# NixieClockv1_1.net
KiCad netlist of a schematic drawn in Altium Designer
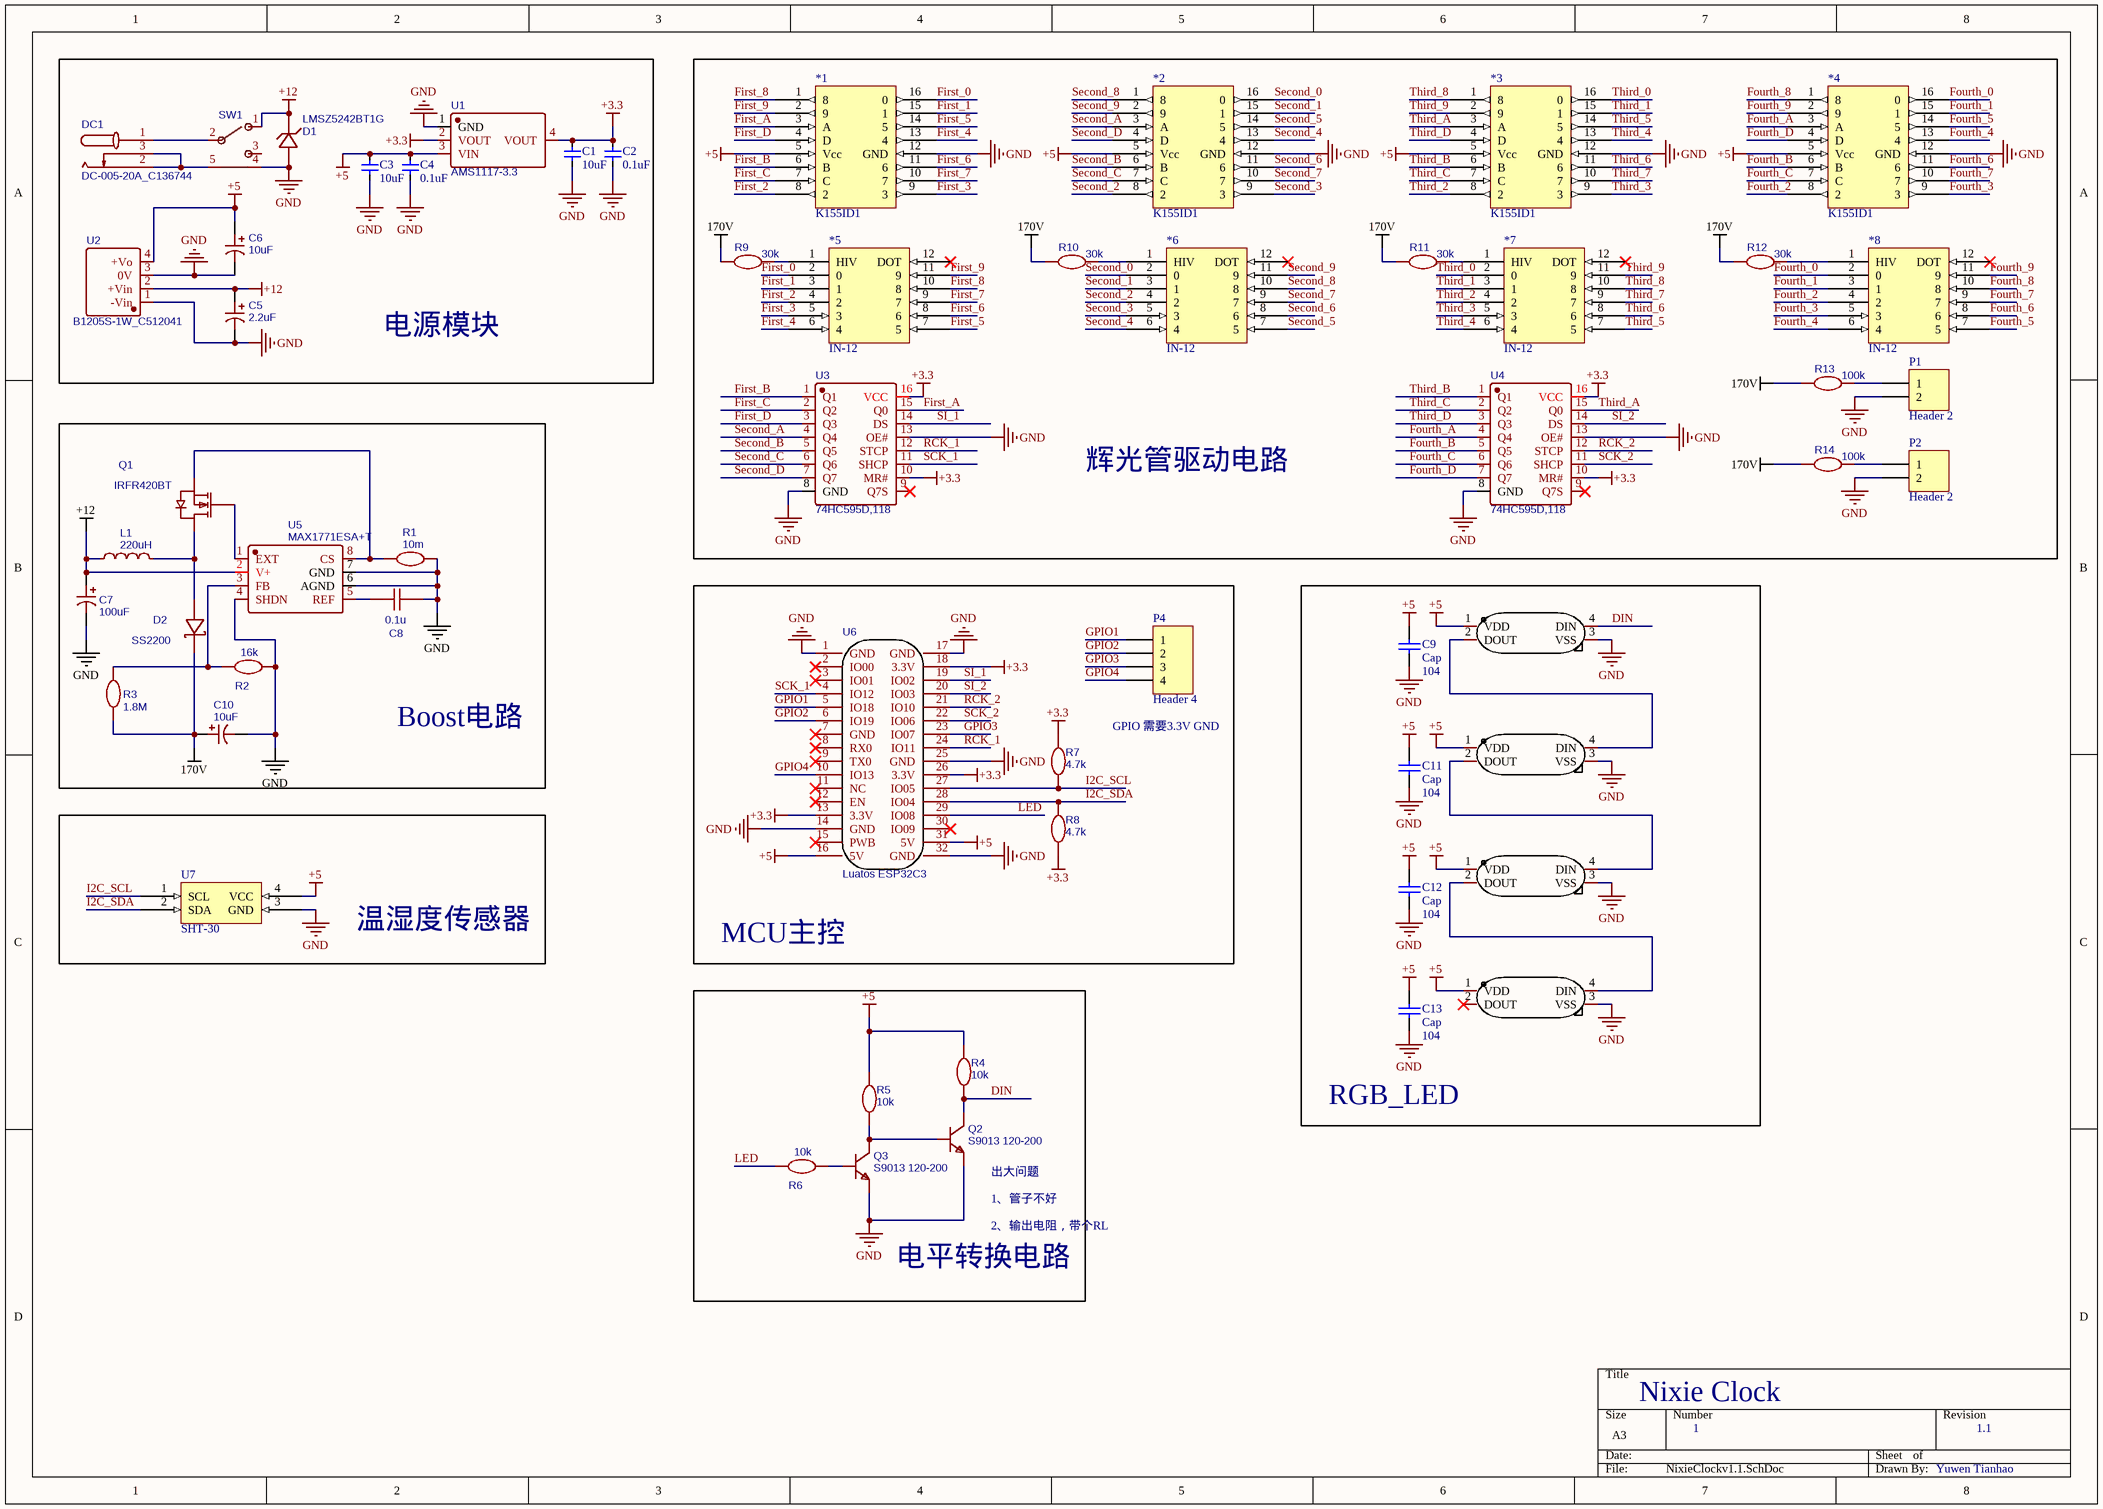
[diagram p0: NixieClockv1.1.SchDoc]

(export (version "E")
  (design (tool "Eeschema 10.0.6"))
  (components
    (comp (ref "*1") (value "K155ID1") (footprint "K155ID1") (libsource (lib "Nixie1") (part "K155ID1")))
    (comp (ref "*2") (value "K155ID1") (footprint "K155ID1") (libsource (lib "Nixie1") (part "K155ID1")))
    (comp (ref "*3") (value "K155ID1") (footprint "K155ID1") (libsource (lib "Nixie1") (part "K155ID1")))
    (comp (ref "*4") (value "K155ID1") (footprint "K155ID1") (libsource (lib "Nixie1") (part "K155ID1")))
    (comp (ref "*5") (value "IN-12") (footprint "IN12") (libsource (lib "Nixie1") (part "IN-12")))
    (comp (ref "*6") (value "IN-12") (footprint "IN12") (libsource (lib "Nixie1") (part "IN-12")))
    (comp (ref "*7") (value "IN-12") (footprint "IN12") (libsource (lib "Nixie1") (part "IN-12")))
    (comp (ref "*8") (value "IN-12") (footprint "IN12") (libsource (lib "Nixie1") (part "IN-12")))
    (comp (ref "C1")
      (value "10uF")
      (footprint "C0805")
      (description "Capacitor")
      (libsource (lib "电容-SCH") (part "C"))
    )
    (comp (ref "C2")
      (value "0.1uF")
      (footprint "0805C")
      (description "Capacitor")
      (libsource (lib "电容-SCH") (part "C"))
    )
    (comp (ref "C3")
      (value "10uF")
      (footprint "0805C")
      (description "Capacitor")
      (libsource (lib "电容-SCH") (part "C"))
    )
    (comp (ref "C4")
      (value "0.1uF")
      (footprint "0805C")
      (description "Capacitor")
      (libsource (lib "电容-SCH") (part "C"))
    )
    (comp (ref "C5")
      (value "2.2uF")
      (footprint "CAP-TH_BD8.0-P3.50-D0.5-FD")
      (fields
        (field (name "BOM_SUPPLIER PART") "C2847238")
        (field (name "BOM_MANUFACTURER PART") "LW100M2500814PE4")
        (field (name "CONTRIBUTOR") "LCSC")
      )
      (libsource (lib "Boost1") (part "10uF"))
    )
    (comp (ref "C6")
      (value "10uF")
      (footprint "CAP-TH_BD8.0-P3.50-D0.5-FD")
      (fields
        (field (name "BOM_SUPPLIER PART") "C2847238")
        (field (name "BOM_MANUFACTURER PART") "LW100M2500814PE4")
        (field (name "CONTRIBUTOR") "LCSC")
      )
      (libsource (lib "Boost1") (part "10uF"))
    )
    (comp (ref "C7")
      (value "100uF")
      (footprint "CAP-TH_BD8.0-P3.50-D0.5-FD")
      (fields
        (field (name "BOM_SUPPLIER PART") "C2847238")
        (field (name "BOM_MANUFACTURER PART") "LW100M2500814PE4")
        (field (name "CONTRIBUTOR") "LCSC")
      )
      (libsource (lib "altium-import") (part "root_3_100uF_"))
    )
    (comp (ref "C8")
      (value "0.1u")
      (footprint "0805C")
      (fields (field (name "CONTRIBUTOR") "LCEDA_Lib"))
      (libsource (lib "altium-import") (part "root_0_0.1u_"))
    )
    (comp (ref "C9")
      (value "Cap")
      (footprint "C 0805_M")
      (description "Capacitor")
      (fields (field (name "ALTIUM_VALUE") "104") (field (name "PUBLISHER") "Altium Limited"))
      (libsource (lib "Miscellaneous Devices") (part "Cap"))
    )
    (comp (ref "C10")
      (value "10uF")
      (footprint "CAP-TH_BD8.0-P3.50-D0.5-FD")
      (fields
        (field (name "BOM_SUPPLIER PART") "C2847238")
        (field (name "BOM_MANUFACTURER PART") "LW100M2500814PE4")
        (field (name "CONTRIBUTOR") "LCSC")
      )
      (libsource (lib "altium-import") (part "root_0_10uF_"))
    )
    (comp (ref "C11")
      (value "Cap")
      (footprint "C 0805_M")
      (description "Capacitor")
      (fields (field (name "ALTIUM_VALUE") "104") (field (name "PUBLISHER") "Altium Limited"))
      (libsource (lib "Miscellaneous Devices") (part "Cap"))
    )
    (comp (ref "C12")
      (value "Cap")
      (footprint "C 0805_M")
      (description "Capacitor")
      (fields (field (name "ALTIUM_VALUE") "104") (field (name "PUBLISHER") "Altium Limited"))
      (libsource (lib "Miscellaneous Devices") (part "Cap"))
    )
    (comp (ref "C13")
      (value "Cap")
      (footprint "C 0805_M")
      (description "Capacitor")
      (fields (field (name "ALTIUM_VALUE") "104") (field (name "PUBLISHER") "Altium Limited"))
      (libsource (lib "Miscellaneous Devices") (part "Cap"))
    )
    (comp (ref "D1")
      (value "LMSZ5242BT1G")
      (footprint "SOD-123_L2.7-W1.6-LS3.7-RD")
      (fields (field (name "BOM_SUPPLIER PART") "C124150") (field (name "CONTRIBUTOR") "LCSC"))
      (libsource (lib "Nixie") (part "LMSZ5242BT1G"))
    )
    (comp (ref "D2")
      (value "SS2200")
      (footprint "SMB_L4.6-W3.6-LS5.3-R-RD")
      (fields (field (name "BOM_SUPPLIER PART") "C64997"))
      (libsource (lib "altium-import") (part "root_1_SS2200_"))
    )
    (comp (ref "DC1")
      (value "DC-005-20A_C136744")
      (footprint "DC-IN-TH_DC-005-20A")
      (fields
        (field (name "BOM_MANUFACTURER PART") "DC-005-20A")
        (field (name "BOM_SUPPLIER PART") "C136744")
        (field (name "CONTRIBUTOR") "LCSC")
      )
      (libsource (lib "Nixie") (part "DC-005-20A_C136744"))
    )
    (comp (ref "L1")
      (value "220uH")
      (footprint "IND-SMD_L12.0-W12.0")
      (fields
        (field (name "BOM_SUPPLIER PART") "C182174")
        (field (name "BOM_MANUFACTURER PART") "SLH1207S221MTT")
        (field (name "CONTRIBUTOR") "LCSC")
      )
      (libsource (lib "altium-import") (part "root_0_220uH_"))
    )
    (comp (ref "LED1")
      (value "WS2812B-B")
      (footprint "LED-SMD_4P-L5.0-W5.0-BL_TC5050RGB")
      (fields (field (name "MANUFACTURER") "worldsemi"))
      (libsource (lib "altium-import") (part "root_0_WS2812B-B_"))
    )
    (comp (ref "LED2")
      (value "WS2812B-B")
      (footprint "LED-SMD_4P-L5.0-W5.0-BL_TC5050RGB")
      (fields (field (name "MANUFACTURER") "worldsemi"))
      (libsource (lib "altium-import") (part "root_0_WS2812B-B_"))
    )
    (comp (ref "LED3")
      (value "WS2812B-B")
      (footprint "LED-SMD_4P-L5.0-W5.0-BL_TC5050RGB")
      (fields (field (name "MANUFACTURER") "worldsemi"))
      (libsource (lib "altium-import") (part "root_0_WS2812B-B_"))
    )
    (comp (ref "LED4")
      (value "WS2812B-B")
      (footprint "LED-SMD_4P-L5.0-W5.0-BL_TC5050RGB")
      (fields (field (name "MANUFACTURER") "worldsemi"))
      (libsource (lib "altium-import") (part "root_0_WS2812B-B_"))
    )
    (comp (ref "P1")
      (value "Header 2")
      (footprint "HDR1X2")
      (description "Header, 2-Pin")
      (fields (field (name "PUBLISHER") "Altium Limited"))
      (libsource (lib "Miscellaneous Connectors") (part "Header 2"))
    )
    (comp (ref "P2")
      (value "Header 2")
      (footprint "HDR1X2")
      (description "Header, 2-Pin")
      (fields (field (name "PUBLISHER") "Altium Limited"))
      (libsource (lib "Miscellaneous Connectors") (part "Header 2"))
    )
    (comp (ref "P4")
      (value "Header 4")
      (footprint "HDR1X4")
      (description "Header, 4-Pin")
      (fields (field (name "PUBLISHER") "Altium Limited"))
      (libsource (lib "Miscellaneous Connectors") (part "Header 4"))
    )
    (comp (ref "Q1")
      (value "IRFR420BT")
      (footprint "TO-252-2_L6.5-W6.1-P4.56-LS9.9-BR-CW")
      (fields (field (name "BOM_SUPPLIER PART") "C878947") (field (name "CONTRIBUTOR") "LCSC"))
      (libsource (lib "altium-import") (part "root_2_IRFR420BT_"))
    )
    (comp (ref "Q2")
      (value "S9013 120-200")
      (footprint "SOT-23-3_L2.9-W1.6-P1.90-LS2.8-BR")
      (fields (field (name "BOM_MANUFACTURER PART") "S9013") (field (name "BOM_SUPPLIER PART") "C107404"))
      (libsource (lib "Nixie1") (part "S9013 120-200"))
    )
    (comp (ref "Q3")
      (value "S9013 120-200")
      (footprint "SOT-23-3_L2.9-W1.6-P1.90-LS2.8-BR")
      (fields (field (name "BOM_MANUFACTURER PART") "S9013") (field (name "BOM_SUPPLIER PART") "C107404"))
      (libsource (lib "Nixie1") (part "S9013 120-200"))
    )
    (comp (ref "R1")
      (value "10m")
      (footprint "2512R")
      (fields (field (name "CONTRIBUTOR") "LCEDA_Lib"))
      (libsource (lib "altium-import") (part "root_0_10m_"))
    )
    (comp (ref "R2")
      (value "16k")
      (footprint "0805R")
      (fields (field (name "CONTRIBUTOR") "LCEDA_Lib"))
      (libsource (lib "altium-import") (part "root_2_1.6k_"))
    )
    (comp (ref "R3")
      (value "1.8M")
      (footprint "0805R")
      (fields (field (name "CONTRIBUTOR") "LCEDA_Lib"))
      (libsource (lib "altium-import") (part "root_1_1.8M_"))
    )
    (comp (ref "R4")
      (value "10k")
      (footprint "0805R")
      (fields (field (name "CONTRIBUTOR") "LCEDA_Lib"))
      (libsource (lib "altium-import") (part "root_3_1.6k_"))
    )
    (comp (ref "R5")
      (value "10k")
      (footprint "0805R")
      (fields (field (name "CONTRIBUTOR") "LCEDA_Lib"))
      (libsource (lib "altium-import") (part "root_3_1.6k_"))
    )
    (comp (ref "R6")
      (value "10k")
      (footprint "0805R")
      (fields (field (name "CONTRIBUTOR") "LCEDA_Lib"))
      (libsource (lib "altium-import") (part "root_2_1.6k_"))
    )
    (comp (ref "R7")
      (value "4.7k")
      (footprint "0805R")
      (fields (field (name "CONTRIBUTOR") "LCEDA_Lib"))
      (libsource (lib "altium-import") (part "root_3_1.6k_"))
    )
    (comp (ref "R8")
      (value "4.7k")
      (footprint "0805R")
      (fields (field (name "CONTRIBUTOR") "LCEDA_Lib"))
      (libsource (lib "altium-import") (part "root_1_1.6k_"))
    )
    (comp (ref "R9")
      (value "30k")
      (footprint "0805R")
      (fields (field (name "CONTRIBUTOR") "LCEDA_Lib"))
      (libsource (lib "altium-import") (part "root_0_1.6k_"))
    )
    (comp (ref "R10")
      (value "30k")
      (footprint "0805R")
      (fields (field (name "CONTRIBUTOR") "LCEDA_Lib"))
      (libsource (lib "altium-import") (part "root_0_1.6k_"))
    )
    (comp (ref "R11")
      (value "30k")
      (footprint "0805R")
      (fields (field (name "CONTRIBUTOR") "LCEDA_Lib"))
      (libsource (lib "altium-import") (part "root_0_1.6k_"))
    )
    (comp (ref "R12")
      (value "30k")
      (footprint "0805R")
      (fields (field (name "CONTRIBUTOR") "LCEDA_Lib"))
      (libsource (lib "altium-import") (part "root_0_1.6k_"))
    )
    (comp (ref "R13")
      (value "100k")
      (footprint "0805R")
      (fields (field (name "CONTRIBUTOR") "LCEDA_Lib"))
      (libsource (lib "altium-import") (part "root_0_1.6k_"))
    )
    (comp (ref "R14")
      (value "100k")
      (footprint "0805R")
      (fields (field (name "CONTRIBUTOR") "LCEDA_Lib"))
      (libsource (lib "altium-import") (part "root_0_1.6k_"))
    )
    (comp (ref "SW1")
      (value "~")
      (footprint "SW-TH_ST-0-102-C03-N003-RS")
      (fields
        (field (name "BOM_SUPPLIER PART") "C1788489")
        (field (name "BOM_MANUFACTURER PART") "ST-0-102-C03-N003-RS")
        (field (name "CONTRIBUTOR") "LCSC")
      )
      (libsource (lib "Nixie") (part "ST-0-102-C03-N003-RS"))
    )
    (comp (ref "U1")
      (value "AMS1117-3.3")
      (footprint "SOT-223-3_L6.5-W3.4-P2.30-LS7.0-BR")
      (fields (field (name "BOM_SUPPLIER PART") "C6186"))
      (libsource (lib "Nixie1") (part "AMS1117-3.3"))
    )
    (comp (ref "U2")
      (value "B1205S-1W_C512041")
      (footprint "PWRM-TH_BXXXXS-1W")
      (fields
        (field (name "BOM_SUPPLIER PART") "C512041")
        (field (name "BOM_MANUFACTURER PART") "B1205S-1W")
        (field (name "CONTRIBUTOR") "LCSC")
      )
      (libsource (lib "Nixie") (part "B1205S-1W_C512041"))
    )
    (comp (ref "U3")
      (value "74HC595D,118")
      (footprint "SOIC-16_L9.9-W3.9-P1.27-LS6.0-BL")
      (fields (field (name "BOM_SUPPLIER PART") "C5947"))
      (libsource (lib "Nixie1") (part "74HC595D,118"))
    )
    (comp (ref "U4")
      (value "74HC595D,118")
      (footprint "SOIC-16_L9.9-W3.9-P1.27-LS6.0-BL")
      (fields (field (name "BOM_SUPPLIER PART") "C5947"))
      (libsource (lib "Nixie1") (part "74HC595D,118"))
    )
    (comp (ref "U5")
      (value "MAX1771ESA+T")
      (footprint "SO-8_L4.9-W3.9-P1.27-LS6.0-BL")
      (fields (field (name "BOM_SUPPLIER PART") "C407903") (field (name "CONTRIBUTOR") "LCSC"))
      (libsource (lib "altium-import") (part "root_0_MAX1771ESA+T_"))
    )
    (comp (ref "U6")
      (value "Luatos ESP32C3")
      (footprint "LUATOS-ESP32C3")
      (fields (field (name "CONTRIBUTOR") "KagurazakaTsuki"))
      (libsource (lib "ESP32C3") (part "Luatos ESP32C3"))
    )
    (comp (ref "U7") (value "SHT-30") (footprint "HDR1X4") (libsource (lib "Boost1") (part "SHT-30")))
  )
  (nets
    (net (code "1") (name "+3.3") (class "Default")
      (node (ref "C1") (pin "2") (pinfunction "2_2") (pintype "passive"))
      (node (ref "C2") (pin "2") (pinfunction "2_2") (pintype "passive"))
      (node (ref "R7") (pin "1") (pinfunction "1_1") (pintype "passive"))
      (node (ref "R8") (pin "1") (pinfunction "1_1") (pintype "passive"))
      (node (ref "U1") (pin "2") (pinfunction "VOUT_2") (pintype "passive"))
      (node (ref "U1") (pin "4") (pinfunction "VOUT_4") (pintype "passive"))
      (node (ref "U3") (pin "10") (pinfunction "MR#_10") (pintype "passive"))
      (node (ref "U3") (pin "16") (pinfunction "VCC_16") (pintype "passive"))
      (node (ref "U4") (pin "10") (pinfunction "MR#_10") (pintype "passive"))
      (node (ref "U4") (pin "16") (pinfunction "VCC_16") (pintype "passive"))
      (node (ref "U6") (pin "13") (pinfunction "3.3V_13") (pintype "passive"))
      (node (ref "U6") (pin "18") (pinfunction "3.3V_18") (pintype "passive"))
      (node (ref "U6") (pin "26") (pinfunction "3.3V_26") (pintype "passive"))
    )
    (net (code "2") (name "+5") (class "Default")
      (node (ref "*1") (pin "5") (pinfunction "Vcc_5") (pintype "input"))
      (node (ref "*2") (pin "5") (pinfunction "Vcc_5") (pintype "input"))
      (node (ref "*3") (pin "5") (pinfunction "Vcc_5") (pintype "input"))
      (node (ref "*4") (pin "5") (pinfunction "Vcc_5") (pintype "input"))
      (node (ref "C11") (pin "2") (pinfunction "2_2") (pintype "passive"))
      (node (ref "C12") (pin "2") (pinfunction "2_2") (pintype "passive"))
      (node (ref "C13") (pin "2") (pinfunction "2_2") (pintype "passive"))
      (node (ref "C3") (pin "2") (pinfunction "2_2") (pintype "passive"))
      (node (ref "C4") (pin "2") (pinfunction "2_2") (pintype "passive"))
      (node (ref "C6") (pin "1") (pinfunction "1_1") (pintype "passive"))
      (node (ref "C9") (pin "2") (pinfunction "2_2") (pintype "passive"))
      (node (ref "LED1") (pin "1") (pinfunction "VDD_1") (pintype "passive"))
      (node (ref "LED2") (pin "1") (pinfunction "VDD_1") (pintype "passive"))
      (node (ref "LED3") (pin "1") (pinfunction "VDD_1") (pintype "passive"))
      (node (ref "LED4") (pin "1") (pinfunction "VDD_1") (pintype "passive"))
      (node (ref "R4") (pin "1") (pinfunction "1_1") (pintype "passive"))
      (node (ref "R5") (pin "1") (pinfunction "1_1") (pintype "passive"))
      (node (ref "U1") (pin "3") (pinfunction "VIN_3") (pintype "passive"))
      (node (ref "U2") (pin "4") (pinfunction "+Vo_4") (pintype "passive"))
      (node (ref "U6") (pin "16") (pinfunction "5V_16") (pintype "passive"))
      (node (ref "U6") (pin "31") (pinfunction "5V_31") (pintype "passive"))
      (node (ref "U7") (pin "4") (pinfunction "VCC_4") (pintype "input"))
    )
    (net (code "3") (name "+12") (class "Default")
      (node (ref "C5") (pin "1") (pinfunction "1_1") (pintype "passive"))
      (node (ref "C7") (pin "1") (pinfunction "1_1") (pintype "passive"))
      (node (ref "D1") (pin "1") (pinfunction "C_1") (pintype "passive"))
      (node (ref "L1") (pin "1") (pinfunction "1_1") (pintype "passive"))
      (node (ref "SW1") (pin "1") (pinfunction "1_1") (pintype "passive"))
      (node (ref "U2") (pin "2") (pinfunction "+Vin_2") (pintype "passive"))
      (node (ref "U5") (pin "2") (pinfunction "V+_2") (pintype "passive"))
    )
    (net (code "4") (name "/DIN") (class "Default")
      (node (ref "LED1") (pin "4") (pinfunction "DIN_4") (pintype "passive"))
      (node (ref "Q2") (pin "3") (pinfunction "3_3") (pintype "passive"))
      (node (ref "R4") (pin "2") (pinfunction "2_2") (pintype "passive"))
    )
    (net (code "5") (name "/First_0") (class "Default")
      (node (ref "*1") (pin "16") (pinfunction "0_16") (pintype "output"))
      (node (ref "*5") (pin "2") (pinfunction "0_2") (pintype "passive"))
    )
    (net (code "6") (name "/First_1") (class "Default")
      (node (ref "*1") (pin "15") (pinfunction "1_15") (pintype "output"))
      (node (ref "*5") (pin "3") (pinfunction "1_3") (pintype "passive"))
    )
    (net (code "7") (name "/First_2") (class "Default")
      (node (ref "*1") (pin "8") (pinfunction "2_8") (pintype "output"))
      (node (ref "*5") (pin "4") (pinfunction "2_4") (pintype "passive"))
    )
    (net (code "8") (name "/First_3") (class "Default")
      (node (ref "*1") (pin "9") (pinfunction "3_9") (pintype "output"))
      (node (ref "*5") (pin "5") (pinfunction "3_5") (pintype "input"))
    )
    (net (code "9") (name "/First_4") (class "Default")
      (node (ref "*1") (pin "13") (pinfunction "4_13") (pintype "output"))
      (node (ref "*5") (pin "6") (pinfunction "4_6") (pintype "input"))
    )
    (net (code "10") (name "/First_5") (class "Default")
      (node (ref "*1") (pin "14") (pinfunction "5_14") (pintype "output"))
      (node (ref "*5") (pin "7") (pinfunction "5_7") (pintype "input"))
    )
    (net (code "11") (name "/First_6") (class "Default")
      (node (ref "*1") (pin "11") (pinfunction "6_11") (pintype "output"))
      (node (ref "*5") (pin "8") (pinfunction "6_8") (pintype "input"))
    )
    (net (code "12") (name "/First_7") (class "Default")
      (node (ref "*1") (pin "10") (pinfunction "7_10") (pintype "output"))
      (node (ref "*5") (pin "9") (pinfunction "7_9") (pintype "input"))
    )
    (net (code "13") (name "/First_8") (class "Default")
      (node (ref "*1") (pin "1") (pinfunction "8_1") (pintype "output"))
      (node (ref "*5") (pin "10") (pinfunction "8_10") (pintype "input"))
    )
    (net (code "14") (name "/First_9") (class "Default")
      (node (ref "*1") (pin "2") (pinfunction "9_2") (pintype "output"))
      (node (ref "*5") (pin "11") (pinfunction "9_11") (pintype "input"))
    )
    (net (code "15") (name "/First_A") (class "Default")
      (node (ref "*1") (pin "3") (pinfunction "A_3") (pintype "input"))
      (node (ref "U3") (pin "15") (pinfunction "Q0_15") (pintype "passive"))
    )
    (net (code "16") (name "/First_B") (class "Default")
      (node (ref "*1") (pin "6") (pinfunction "B_6") (pintype "input"))
      (node (ref "U3") (pin "1") (pinfunction "Q1_1") (pintype "passive"))
    )
    (net (code "17") (name "/First_C") (class "Default")
      (node (ref "*1") (pin "7") (pinfunction "C_7") (pintype "input"))
      (node (ref "U3") (pin "2") (pinfunction "Q2_2") (pintype "passive"))
    )
    (net (code "18") (name "/First_D") (class "Default")
      (node (ref "*1") (pin "4") (pinfunction "D_4") (pintype "input"))
      (node (ref "U3") (pin "3") (pinfunction "Q3_3") (pintype "passive"))
    )
    (net (code "19") (name "/Fourth_0") (class "Default")
      (node (ref "*4") (pin "16") (pinfunction "0_16") (pintype "output"))
      (node (ref "*8") (pin "2") (pinfunction "0_2") (pintype "passive"))
    )
    (net (code "20") (name "/Fourth_1") (class "Default")
      (node (ref "*4") (pin "15") (pinfunction "1_15") (pintype "output"))
      (node (ref "*8") (pin "3") (pinfunction "1_3") (pintype "passive"))
    )
    (net (code "21") (name "/Fourth_2") (class "Default")
      (node (ref "*4") (pin "8") (pinfunction "2_8") (pintype "output"))
      (node (ref "*8") (pin "4") (pinfunction "2_4") (pintype "passive"))
    )
    (net (code "22") (name "/Fourth_3") (class "Default")
      (node (ref "*4") (pin "9") (pinfunction "3_9") (pintype "output"))
      (node (ref "*8") (pin "5") (pinfunction "3_5") (pintype "input"))
    )
    (net (code "23") (name "/Fourth_4") (class "Default")
      (node (ref "*4") (pin "13") (pinfunction "4_13") (pintype "output"))
      (node (ref "*8") (pin "6") (pinfunction "4_6") (pintype "input"))
    )
    (net (code "24") (name "/Fourth_5") (class "Default")
      (node (ref "*4") (pin "14") (pinfunction "5_14") (pintype "output"))
      (node (ref "*8") (pin "7") (pinfunction "5_7") (pintype "input"))
    )
    (net (code "25") (name "/Fourth_6") (class "Default")
      (node (ref "*4") (pin "11") (pinfunction "6_11") (pintype "output"))
      (node (ref "*8") (pin "8") (pinfunction "6_8") (pintype "input"))
    )
    (net (code "26") (name "/Fourth_7") (class "Default")
      (node (ref "*4") (pin "10") (pinfunction "7_10") (pintype "output"))
      (node (ref "*8") (pin "9") (pinfunction "7_9") (pintype "input"))
    )
    (net (code "27") (name "/Fourth_8") (class "Default")
      (node (ref "*4") (pin "1") (pinfunction "8_1") (pintype "output"))
      (node (ref "*8") (pin "10") (pinfunction "8_10") (pintype "input"))
    )
    (net (code "28") (name "/Fourth_9") (class "Default")
      (node (ref "*4") (pin "2") (pinfunction "9_2") (pintype "output"))
      (node (ref "*8") (pin "11") (pinfunction "9_11") (pintype "input"))
    )
    (net (code "29") (name "/Fourth_A") (class "Default")
      (node (ref "*4") (pin "3") (pinfunction "A_3") (pintype "input"))
      (node (ref "U4") (pin "4") (pinfunction "Q4_4") (pintype "passive"))
    )
    (net (code "30") (name "/Fourth_B") (class "Default")
      (node (ref "*4") (pin "6") (pinfunction "B_6") (pintype "input"))
      (node (ref "U4") (pin "5") (pinfunction "Q5_5") (pintype "passive"))
    )
    (net (code "31") (name "/Fourth_C") (class "Default")
      (node (ref "*4") (pin "7") (pinfunction "C_7") (pintype "input"))
      (node (ref "U4") (pin "6") (pinfunction "Q6_6") (pintype "passive"))
    )
    (net (code "32") (name "/Fourth_D") (class "Default")
      (node (ref "*4") (pin "4") (pinfunction "D_4") (pintype "input"))
      (node (ref "U4") (pin "7") (pinfunction "Q7_7") (pintype "passive"))
    )
    (net (code "33") (name "/GPIO1") (class "Default")
      (node (ref "P4") (pin "1") (pinfunction "1_1") (pintype "passive"))
      (node (ref "U6") (pin "5") (pinfunction "IO18_5") (pintype "passive"))
    )
    (net (code "34") (name "/GPIO2") (class "Default")
      (node (ref "P4") (pin "2") (pinfunction "2_2") (pintype "passive"))
      (node (ref "U6") (pin "6") (pinfunction "IO19_6") (pintype "passive"))
    )
    (net (code "35") (name "/GPIO3") (class "Default")
      (node (ref "P4") (pin "3") (pinfunction "3_3") (pintype "passive"))
      (node (ref "U6") (pin "23") (pinfunction "IO07_23") (pintype "passive"))
    )
    (net (code "36") (name "/GPIO4") (class "Default")
      (node (ref "P4") (pin "4") (pinfunction "4_4") (pintype "passive"))
      (node (ref "U6") (pin "10") (pinfunction "IO13_10") (pintype "passive"))
    )
    (net (code "37") (name "/I2C_SCL") (class "Default")
      (node (ref "R7") (pin "2") (pinfunction "2_2") (pintype "passive"))
      (node (ref "U6") (pin "27") (pinfunction "IO05_27") (pintype "passive"))
      (node (ref "U7") (pin "1") (pinfunction "SCL_1") (pintype "input"))
    )
    (net (code "38") (name "/I2C_SDA") (class "Default")
      (node (ref "R8") (pin "2") (pinfunction "2_2") (pintype "passive"))
      (node (ref "U6") (pin "28") (pinfunction "IO04_28") (pintype "passive"))
      (node (ref "U7") (pin "2") (pinfunction "SDA_2") (pintype "input"))
    )
    (net (code "39") (name "/LED") (class "Default")
      (node (ref "R6") (pin "2") (pinfunction "2_2") (pintype "passive"))
      (node (ref "U6") (pin "29") (pinfunction "IO08_29") (pintype "passive"))
    )
    (net (code "40") (name "/RCK_1") (class "Default")
      (node (ref "U3") (pin "12") (pinfunction "STCP_12") (pintype "passive"))
      (node (ref "U6") (pin "24") (pinfunction "IO11_24") (pintype "passive"))
    )
    (net (code "41") (name "/RCK_2") (class "Default")
      (node (ref "U4") (pin "12") (pinfunction "STCP_12") (pintype "passive"))
      (node (ref "U6") (pin "21") (pinfunction "IO10_21") (pintype "passive"))
    )
    (net (code "42") (name "/SCK_1") (class "Default")
      (node (ref "U3") (pin "11") (pinfunction "SHCP_11") (pintype "passive"))
      (node (ref "U6") (pin "4") (pinfunction "IO12_4") (pintype "passive"))
    )
    (net (code "43") (name "/SCK_2") (class "Default")
      (node (ref "U4") (pin "11") (pinfunction "SHCP_11") (pintype "passive"))
      (node (ref "U6") (pin "22") (pinfunction "IO06_22") (pintype "passive"))
    )
    (net (code "44") (name "/SI_1") (class "Default")
      (node (ref "U3") (pin "14") (pinfunction "DS_14") (pintype "passive"))
      (node (ref "U6") (pin "19") (pinfunction "IO02_19") (pintype "passive"))
    )
    (net (code "45") (name "/SI_2") (class "Default")
      (node (ref "U4") (pin "14") (pinfunction "DS_14") (pintype "passive"))
      (node (ref "U6") (pin "20") (pinfunction "IO03_20") (pintype "passive"))
    )
    (net (code "46") (name "/Second_0") (class "Default")
      (node (ref "*2") (pin "16") (pinfunction "0_16") (pintype "output"))
      (node (ref "*6") (pin "2") (pinfunction "0_2") (pintype "passive"))
    )
    (net (code "47") (name "/Second_1") (class "Default")
      (node (ref "*2") (pin "15") (pinfunction "1_15") (pintype "output"))
      (node (ref "*6") (pin "3") (pinfunction "1_3") (pintype "passive"))
    )
    (net (code "48") (name "/Second_2") (class "Default")
      (node (ref "*2") (pin "8") (pinfunction "2_8") (pintype "output"))
      (node (ref "*6") (pin "4") (pinfunction "2_4") (pintype "passive"))
    )
    (net (code "49") (name "/Second_3") (class "Default")
      (node (ref "*2") (pin "9") (pinfunction "3_9") (pintype "output"))
      (node (ref "*6") (pin "5") (pinfunction "3_5") (pintype "input"))
    )
    (net (code "50") (name "/Second_4") (class "Default")
      (node (ref "*2") (pin "13") (pinfunction "4_13") (pintype "output"))
      (node (ref "*6") (pin "6") (pinfunction "4_6") (pintype "input"))
    )
    (net (code "51") (name "/Second_5") (class "Default")
      (node (ref "*2") (pin "14") (pinfunction "5_14") (pintype "output"))
      (node (ref "*6") (pin "7") (pinfunction "5_7") (pintype "input"))
    )
    (net (code "52") (name "/Second_6") (class "Default")
      (node (ref "*2") (pin "11") (pinfunction "6_11") (pintype "output"))
      (node (ref "*6") (pin "8") (pinfunction "6_8") (pintype "input"))
    )
    (net (code "53") (name "/Second_7") (class "Default")
      (node (ref "*2") (pin "10") (pinfunction "7_10") (pintype "output"))
      (node (ref "*6") (pin "9") (pinfunction "7_9") (pintype "input"))
    )
    (net (code "54") (name "/Second_8") (class "Default")
      (node (ref "*2") (pin "1") (pinfunction "8_1") (pintype "output"))
      (node (ref "*6") (pin "10") (pinfunction "8_10") (pintype "input"))
    )
    (net (code "55") (name "/Second_9") (class "Default")
      (node (ref "*2") (pin "2") (pinfunction "9_2") (pintype "output"))
      (node (ref "*6") (pin "11") (pinfunction "9_11") (pintype "input"))
    )
    (net (code "56") (name "/Second_A") (class "Default")
      (node (ref "*2") (pin "3") (pinfunction "A_3") (pintype "input"))
      (node (ref "U3") (pin "4") (pinfunction "Q4_4") (pintype "passive"))
    )
    (net (code "57") (name "/Second_B") (class "Default")
      (node (ref "*2") (pin "6") (pinfunction "B_6") (pintype "input"))
      (node (ref "U3") (pin "5") (pinfunction "Q5_5") (pintype "passive"))
    )
    (net (code "58") (name "/Second_C") (class "Default")
      (node (ref "*2") (pin "7") (pinfunction "C_7") (pintype "input"))
      (node (ref "U3") (pin "6") (pinfunction "Q6_6") (pintype "passive"))
    )
    (net (code "59") (name "/Second_D") (class "Default")
      (node (ref "*2") (pin "4") (pinfunction "D_4") (pintype "input"))
      (node (ref "U3") (pin "7") (pinfunction "Q7_7") (pintype "passive"))
    )
    (net (code "60") (name "/Third_0") (class "Default")
      (node (ref "*3") (pin "16") (pinfunction "0_16") (pintype "output"))
      (node (ref "*7") (pin "2") (pinfunction "0_2") (pintype "passive"))
    )
    (net (code "61") (name "/Third_1") (class "Default")
      (node (ref "*3") (pin "15") (pinfunction "1_15") (pintype "output"))
      (node (ref "*7") (pin "3") (pinfunction "1_3") (pintype "passive"))
    )
    (net (code "62") (name "/Third_2") (class "Default")
      (node (ref "*3") (pin "8") (pinfunction "2_8") (pintype "output"))
      (node (ref "*7") (pin "4") (pinfunction "2_4") (pintype "passive"))
    )
    (net (code "63") (name "/Third_3") (class "Default")
      (node (ref "*3") (pin "9") (pinfunction "3_9") (pintype "output"))
      (node (ref "*7") (pin "5") (pinfunction "3_5") (pintype "input"))
    )
    (net (code "64") (name "/Third_4") (class "Default")
      (node (ref "*3") (pin "13") (pinfunction "4_13") (pintype "output"))
      (node (ref "*7") (pin "6") (pinfunction "4_6") (pintype "input"))
    )
    (net (code "65") (name "/Third_5") (class "Default")
      (node (ref "*3") (pin "14") (pinfunction "5_14") (pintype "output"))
      (node (ref "*7") (pin "7") (pinfunction "5_7") (pintype "input"))
    )
    (net (code "66") (name "/Third_6") (class "Default")
      (node (ref "*3") (pin "11") (pinfunction "6_11") (pintype "output"))
      (node (ref "*7") (pin "8") (pinfunction "6_8") (pintype "input"))
    )
    (net (code "67") (name "/Third_7") (class "Default")
      (node (ref "*3") (pin "10") (pinfunction "7_10") (pintype "output"))
      (node (ref "*7") (pin "9") (pinfunction "7_9") (pintype "input"))
    )
    (net (code "68") (name "/Third_8") (class "Default")
      (node (ref "*3") (pin "1") (pinfunction "8_1") (pintype "output"))
      (node (ref "*7") (pin "10") (pinfunction "8_10") (pintype "input"))
    )
    (net (code "69") (name "/Third_9") (class "Default")
      (node (ref "*3") (pin "2") (pinfunction "9_2") (pintype "output"))
      (node (ref "*7") (pin "11") (pinfunction "9_11") (pintype "input"))
    )
    (net (code "70") (name "/Third_A") (class "Default")
      (node (ref "*3") (pin "3") (pinfunction "A_3") (pintype "input"))
      (node (ref "U4") (pin "15") (pinfunction "Q0_15") (pintype "passive"))
    )
    (net (code "71") (name "/Third_B") (class "Default")
      (node (ref "*3") (pin "6") (pinfunction "B_6") (pintype "input"))
      (node (ref "U4") (pin "1") (pinfunction "Q1_1") (pintype "passive"))
    )
    (net (code "72") (name "/Third_C") (class "Default")
      (node (ref "*3") (pin "7") (pinfunction "C_7") (pintype "input"))
      (node (ref "U4") (pin "2") (pinfunction "Q2_2") (pintype "passive"))
    )
    (net (code "73") (name "/Third_D") (class "Default")
      (node (ref "*3") (pin "4") (pinfunction "D_4") (pintype "input"))
      (node (ref "U4") (pin "3") (pinfunction "Q3_3") (pintype "passive"))
    )
    (net (code "74") (name "170V") (class "Default")
      (node (ref "C10") (pin "1") (pinfunction "1_1") (pintype "passive"))
      (node (ref "D2") (pin "2") (pinfunction "K_2") (pintype "passive"))
      (node (ref "R10") (pin "1") (pinfunction "1_1") (pintype "passive"))
      (node (ref "R11") (pin "1") (pinfunction "1_1") (pintype "passive"))
      (node (ref "R12") (pin "1") (pinfunction "1_1") (pintype "passive"))
      (node (ref "R13") (pin "1") (pinfunction "1_1") (pintype "passive"))
      (node (ref "R14") (pin "1") (pinfunction "1_1") (pintype "passive"))
      (node (ref "R3") (pin "1") (pinfunction "1_1") (pintype "passive"))
      (node (ref "R9") (pin "1") (pinfunction "1_1") (pintype "passive"))
    )
    (net (code "75") (name "GND") (class "Default")
      (node (ref "*1") (pin "12") (pinfunction "GND_12") (pintype "input"))
      (node (ref "*2") (pin "12") (pinfunction "GND_12") (pintype "input"))
      (node (ref "*3") (pin "12") (pinfunction "GND_12") (pintype "input"))
      (node (ref "*4") (pin "12") (pinfunction "GND_12") (pintype "input"))
      (node (ref "C1") (pin "1") (pinfunction "1_1") (pintype "passive"))
      (node (ref "C10") (pin "2") (pinfunction "2_2") (pintype "passive"))
      (node (ref "C11") (pin "1") (pinfunction "1_1") (pintype "passive"))
      (node (ref "C12") (pin "1") (pinfunction "1_1") (pintype "passive"))
      (node (ref "C13") (pin "1") (pinfunction "1_1") (pintype "passive"))
      (node (ref "C2") (pin "1") (pinfunction "1_1") (pintype "passive"))
      (node (ref "C3") (pin "1") (pinfunction "1_1") (pintype "passive"))
      (node (ref "C4") (pin "1") (pinfunction "1_1") (pintype "passive"))
      (node (ref "C5") (pin "2") (pinfunction "2_2") (pintype "passive"))
      (node (ref "C6") (pin "2") (pinfunction "2_2") (pintype "passive"))
      (node (ref "C7") (pin "2") (pinfunction "2_2") (pintype "passive"))
      (node (ref "C8") (pin "2") (pinfunction "2_2") (pintype "passive"))
      (node (ref "C9") (pin "1") (pinfunction "1_1") (pintype "passive"))
      (node (ref "D1") (pin "2") (pinfunction "A_2") (pintype "passive"))
      (node (ref "LED1") (pin "3") (pinfunction "VSS_3") (pintype "passive"))
      (node (ref "LED2") (pin "3") (pinfunction "VSS_3") (pintype "passive"))
      (node (ref "LED3") (pin "3") (pinfunction "VSS_3") (pintype "passive"))
      (node (ref "LED4") (pin "3") (pinfunction "VSS_3") (pintype "passive"))
      (node (ref "P1") (pin "2") (pinfunction "2_2") (pintype "passive"))
      (node (ref "P2") (pin "2") (pinfunction "2_2") (pintype "passive"))
      (node (ref "Q2") (pin "2") (pinfunction "2_2") (pintype "passive"))
      (node (ref "Q3") (pin "2") (pinfunction "2_2") (pintype "passive"))
      (node (ref "R1") (pin "2") (pinfunction "2_2") (pintype "passive"))
      (node (ref "R2") (pin "1") (pinfunction "1_1") (pintype "passive"))
      (node (ref "SW1") (pin "4") (pinfunction "4_4") (pintype "passive"))
      (node (ref "U1") (pin "1") (pinfunction "GND_1") (pintype "passive"))
      (node (ref "U2") (pin "1") (pinfunction "-Vin_1") (pintype "passive"))
      (node (ref "U2") (pin "3") (pinfunction "0V_3") (pintype "passive"))
      (node (ref "U3") (pin "13") (pinfunction "OE#_13") (pintype "passive"))
      (node (ref "U3") (pin "8") (pinfunction "GND_8") (pintype "passive"))
      (node (ref "U4") (pin "13") (pinfunction "OE#_13") (pintype "passive"))
      (node (ref "U4") (pin "8") (pinfunction "GND_8") (pintype "passive"))
      (node (ref "U5") (pin "4") (pinfunction "SHDN_4") (pintype "passive"))
      (node (ref "U5") (pin "6") (pinfunction "AGND_6") (pintype "passive"))
      (node (ref "U5") (pin "7") (pinfunction "GND_7") (pintype "passive"))
      (node (ref "U6") (pin "1") (pinfunction "GND_1") (pintype "passive"))
      (node (ref "U6") (pin "14") (pinfunction "GND_14") (pintype "passive"))
      (node (ref "U6") (pin "17") (pinfunction "GND_17") (pintype "passive"))
      (node (ref "U6") (pin "25") (pinfunction "GND_25") (pintype "passive"))
      (node (ref "U6") (pin "32") (pinfunction "GND_32") (pintype "passive"))
      (node (ref "U7") (pin "3") (pinfunction "GND_3") (pintype "input"))
    )
    (net (code "76") (name "Net-(*5-HIV)") (class "Default")
      (node (ref "*5") (pin "1") (pinfunction "HIV_1") (pintype "passive"))
      (node (ref "R9") (pin "2") (pinfunction "2_2") (pintype "passive"))
    )
    (net (code "77") (name "Net-(*6-HIV)") (class "Default")
      (node (ref "*6") (pin "1") (pinfunction "HIV_1") (pintype "passive"))
      (node (ref "R10") (pin "2") (pinfunction "2_2") (pintype "passive"))
    )
    (net (code "78") (name "Net-(*7-HIV)") (class "Default")
      (node (ref "*7") (pin "1") (pinfunction "HIV_1") (pintype "passive"))
      (node (ref "R11") (pin "2") (pinfunction "2_2") (pintype "passive"))
    )
    (net (code "79") (name "Net-(*8-HIV)") (class "Default")
      (node (ref "*8") (pin "1") (pinfunction "HIV_1") (pintype "passive"))
      (node (ref "R12") (pin "2") (pinfunction "2_2") (pintype "passive"))
    )
    (net (code "80") (name "Net-(D2-A)") (class "Default")
      (node (ref "D2") (pin "1") (pinfunction "A_1") (pintype "passive"))
      (node (ref "L1") (pin "2") (pinfunction "2_2") (pintype "passive"))
      (node (ref "Q1") (pin "2") (pinfunction "D_2") (pintype "passive"))
    )
    (net (code "81") (name "Net-(DC1-Pad1)") (class "Default")
      (node (ref "DC1") (pin "1") (pinfunction "1_1") (pintype "passive"))
      (node (ref "SW1") (pin "2") (pinfunction "2_2") (pintype "passive"))
    )
    (net (code "82") (name "Net-(DC1-Pad2)") (class "Default")
      (node (ref "DC1") (pin "2") (pinfunction "2_2") (pintype "passive"))
      (node (ref "DC1") (pin "3") (pinfunction "3_3") (pintype "passive"))
      (node (ref "SW1") (pin "5") (pinfunction "5_5") (pintype "passive"))
    )
    (net (code "83") (name "Net-(LED1-DOUT)") (class "Default")
      (node (ref "LED1") (pin "2") (pinfunction "DOUT_2") (pintype "passive"))
      (node (ref "LED2") (pin "4") (pinfunction "DIN_4") (pintype "passive"))
    )
    (net (code "84") (name "Net-(LED2-DOUT)") (class "Default")
      (node (ref "LED2") (pin "2") (pinfunction "DOUT_2") (pintype "passive"))
      (node (ref "LED3") (pin "4") (pinfunction "DIN_4") (pintype "passive"))
    )
    (net (code "85") (name "Net-(LED3-DOUT)") (class "Default")
      (node (ref "LED3") (pin "2") (pinfunction "DOUT_2") (pintype "passive"))
      (node (ref "LED4") (pin "4") (pinfunction "DIN_4") (pintype "passive"))
    )
    (net (code "86") (name "Net-(P1-Pad1)") (class "Default")
      (node (ref "P1") (pin "1") (pinfunction "1_1") (pintype "passive"))
      (node (ref "R13") (pin "2") (pinfunction "2_2") (pintype "passive"))
    )
    (net (code "87") (name "Net-(P2-Pad1)") (class "Default")
      (node (ref "P2") (pin "1") (pinfunction "1_1") (pintype "passive"))
      (node (ref "R14") (pin "2") (pinfunction "2_2") (pintype "passive"))
    )
    (net (code "88") (name "Net-(Q1-G)") (class "Default")
      (node (ref "Q1") (pin "1") (pinfunction "G_1") (pintype "passive"))
      (node (ref "U5") (pin "1") (pinfunction "EXT_1") (pintype "passive"))
    )
    (net (code "89") (name "Net-(Q1-S)") (class "Default")
      (node (ref "Q1") (pin "3") (pinfunction "S_3") (pintype "passive"))
      (node (ref "R1") (pin "1") (pinfunction "1_1") (pintype "passive"))
      (node (ref "U5") (pin "8") (pinfunction "CS_8") (pintype "passive"))
    )
    (net (code "90") (name "Net-(Q2-Pad1)") (class "Default")
      (node (ref "Q2") (pin "1") (pinfunction "1_1") (pintype "passive"))
      (node (ref "Q3") (pin "3") (pinfunction "3_3") (pintype "passive"))
      (node (ref "R5") (pin "2") (pinfunction "2_2") (pintype "passive"))
    )
    (net (code "91") (name "Net-(Q3-Pad1)") (class "Default")
      (node (ref "Q3") (pin "1") (pinfunction "1_1") (pintype "passive"))
      (node (ref "R6") (pin "1") (pinfunction "1_1") (pintype "passive"))
    )
    (net (code "92") (name "Net-(U5-FB)") (class "Default")
      (node (ref "R2") (pin "2") (pinfunction "2_2") (pintype "passive"))
      (node (ref "R3") (pin "2") (pinfunction "2_2") (pintype "passive"))
      (node (ref "U5") (pin "3") (pinfunction "FB_3") (pintype "passive"))
    )
    (net (code "93") (name "Net-(U5-REF)") (class "Default")
      (node (ref "C8") (pin "1") (pinfunction "1_1") (pintype "passive"))
      (node (ref "U5") (pin "5") (pinfunction "REF_5") (pintype "passive"))
    )
    (net (code "94") (name "unconnected-(*5-DOT-Pad12)") (class "Default")
      (node (ref "*5") (pin "12") (pinfunction "DOT_12") (pintype "input+no_connect"))
    )
    (net (code "95") (name "unconnected-(*6-DOT-Pad12)") (class "Default")
      (node (ref "*6") (pin "12") (pinfunction "DOT_12") (pintype "input+no_connect"))
    )
    (net (code "96") (name "unconnected-(*7-DOT-Pad12)") (class "Default")
      (node (ref "*7") (pin "12") (pinfunction "DOT_12") (pintype "input+no_connect"))
    )
    (net (code "97") (name "unconnected-(*8-DOT-Pad12)") (class "Default")
      (node (ref "*8") (pin "12") (pinfunction "DOT_12") (pintype "input+no_connect"))
    )
    (net (code "98") (name "unconnected-(LED4-DOUT-Pad2)") (class "Default")
      (node (ref "LED4") (pin "2") (pinfunction "DOUT_2") (pintype "passive+no_connect"))
    )
    (net (code "99") (name "unconnected-(SW1-Pad3)") (class "Default")
      (node (ref "SW1") (pin "3") (pinfunction "3_3") (pintype "passive"))
    )
    (net (code "100") (name "unconnected-(U3-Q7S-Pad9)") (class "Default")
      (node (ref "U3") (pin "9") (pinfunction "Q7S_9") (pintype "passive+no_connect"))
    )
    (net (code "101") (name "unconnected-(U4-Q7S-Pad9)") (class "Default")
      (node (ref "U4") (pin "9") (pinfunction "Q7S_9") (pintype "passive+no_connect"))
    )
    (net (code "102") (name "unconnected-(U6-EN-Pad12)") (class "Default")
      (node (ref "U6") (pin "12") (pinfunction "EN_12") (pintype "passive+no_connect"))
    )
    (net (code "103") (name "unconnected-(U6-GND-Pad7)") (class "Default")
      (node (ref "U6") (pin "7") (pinfunction "GND_7") (pintype "passive+no_connect"))
    )
    (net (code "104") (name "unconnected-(U6-IO00-Pad2)") (class "Default")
      (node (ref "U6") (pin "2") (pinfunction "IO00_2") (pintype "passive+no_connect"))
    )
    (net (code "105") (name "unconnected-(U6-IO01-Pad3)") (class "Default")
      (node (ref "U6") (pin "3") (pinfunction "IO01_3") (pintype "passive+no_connect"))
    )
    (net (code "106") (name "unconnected-(U6-IO09-Pad30)") (class "Default")
      (node (ref "U6") (pin "30") (pinfunction "IO09_30") (pintype "passive+no_connect"))
    )
    (net (code "107") (name "unconnected-(U6-NC-Pad11)") (class "Default")
      (node (ref "U6") (pin "11") (pinfunction "NC_11") (pintype "passive+no_connect"))
    )
    (net (code "108") (name "unconnected-(U6-PWB-Pad15)") (class "Default")
      (node (ref "U6") (pin "15") (pinfunction "PWB_15") (pintype "passive+no_connect"))
    )
    (net (code "109") (name "unconnected-(U6-RX0-Pad8)") (class "Default")
      (node (ref "U6") (pin "8") (pinfunction "RX0_8") (pintype "passive+no_connect"))
    )
    (net (code "110") (name "unconnected-(U6-TX0-Pad9)") (class "Default")
      (node (ref "U6") (pin "9") (pinfunction "TX0_9") (pintype "passive+no_connect"))
    )
  )
)
